# KeyboardMain.net
KiCad netlist of a schematic drawn in Altium Designer
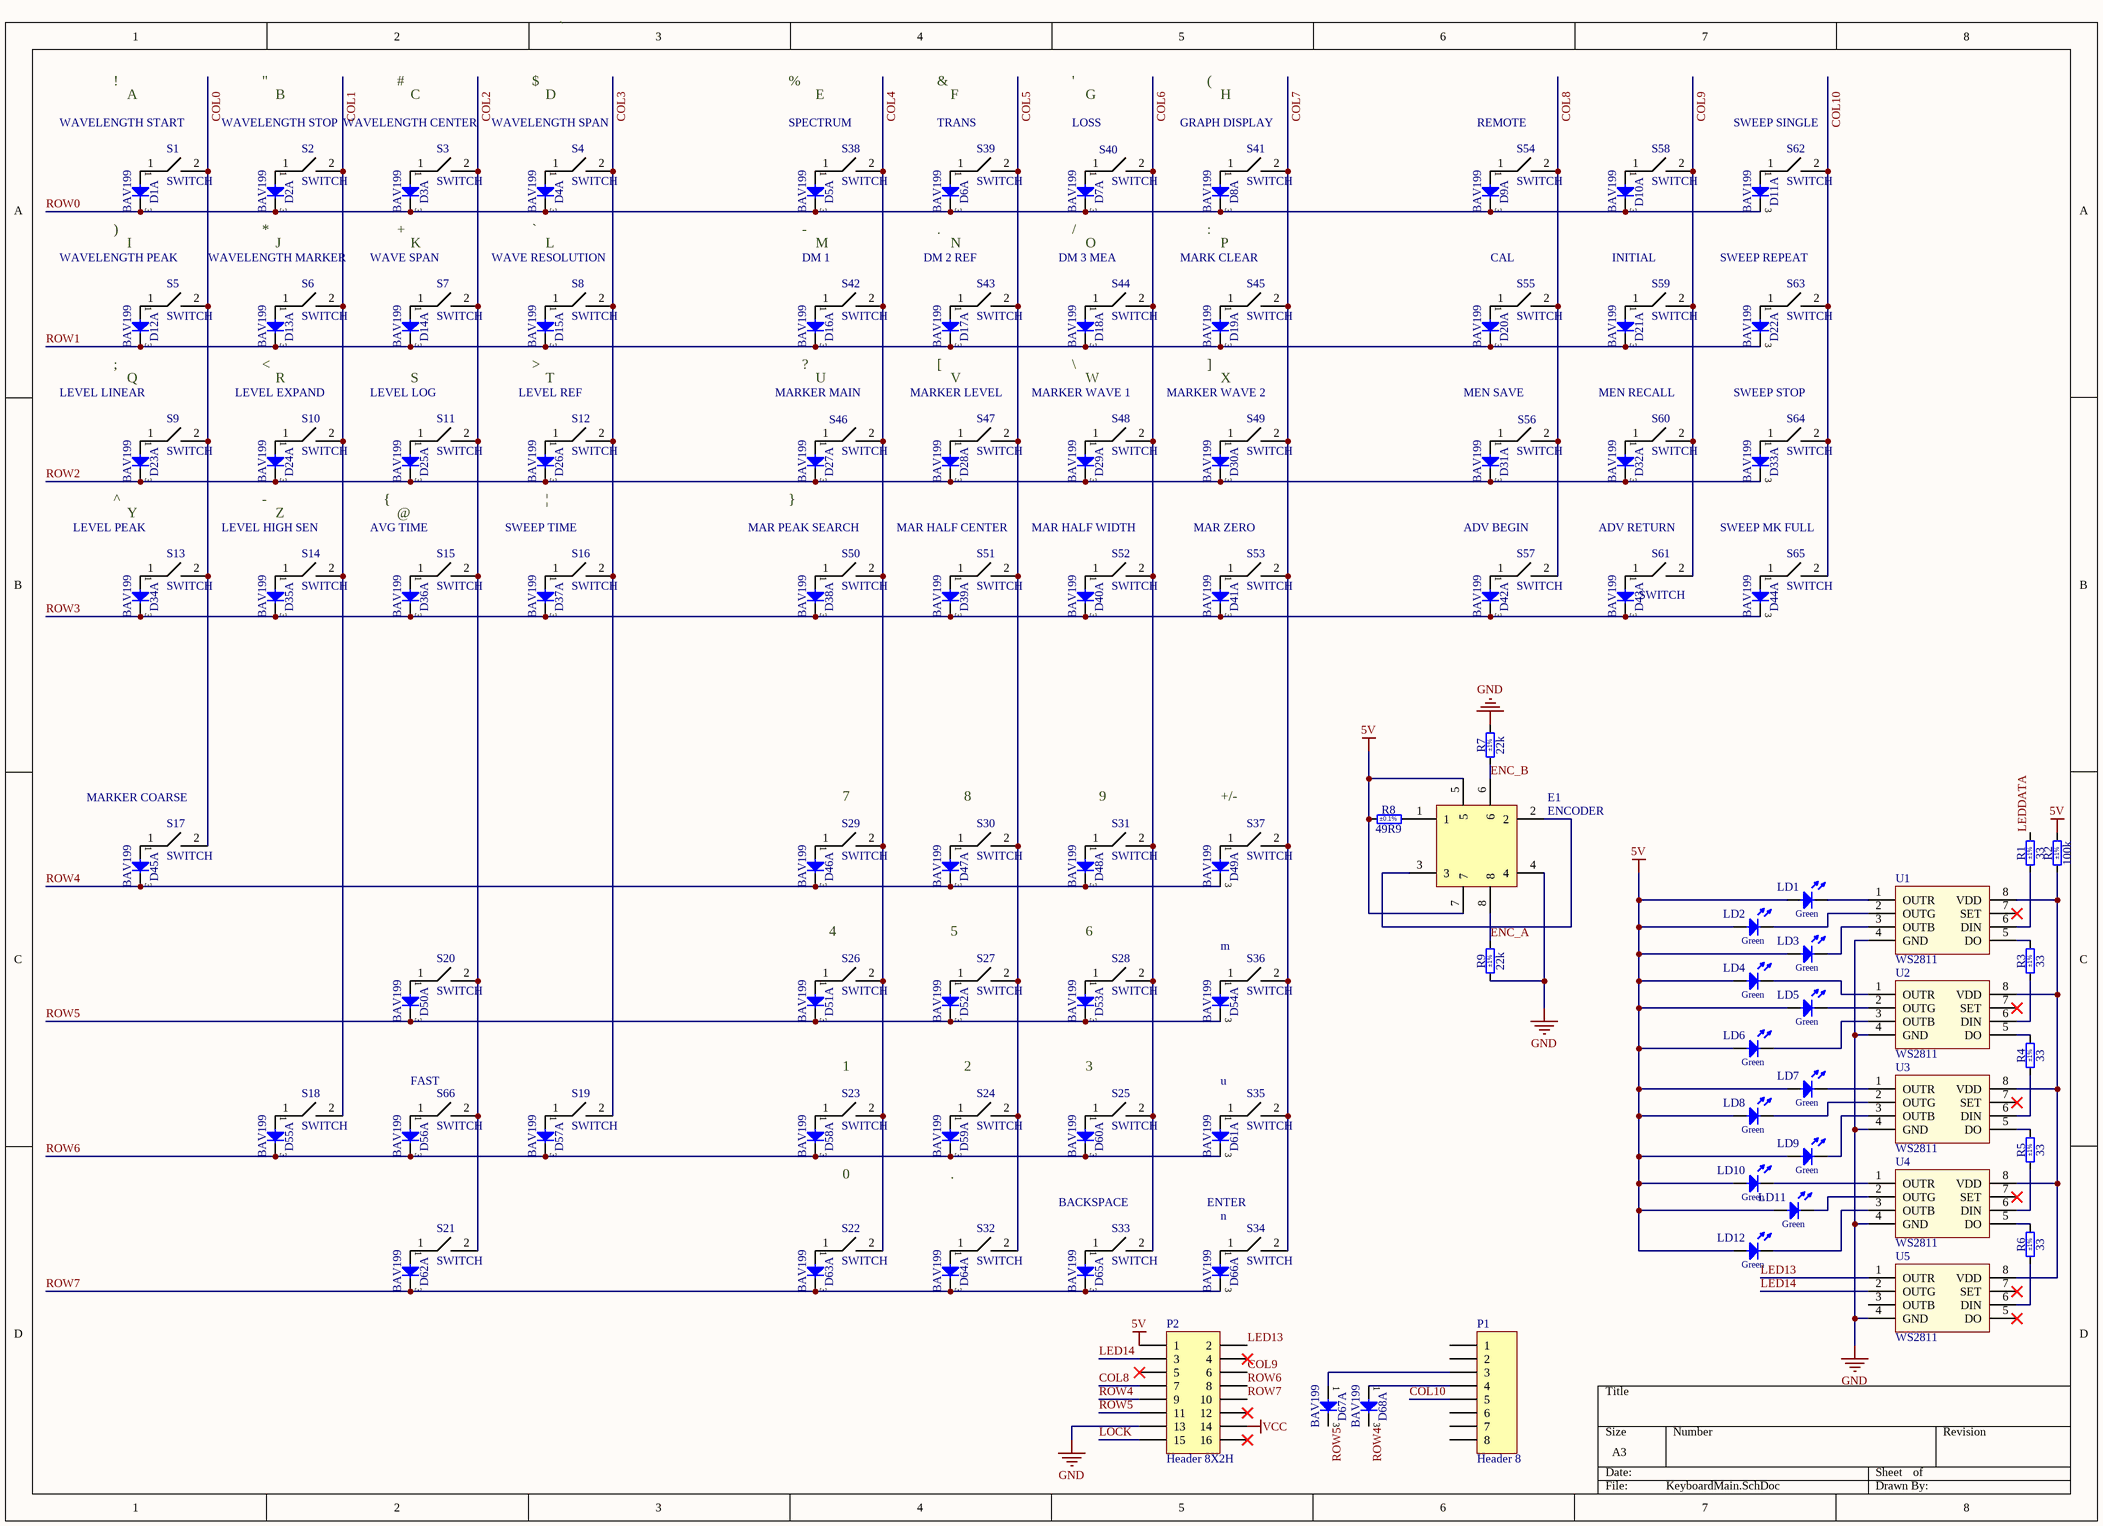
[diagram p0: KeyboardMain.SchDoc]

(export (version "E")
  (design (tool "Eeschema 10.0.6"))
  (components
    (comp (ref "D1")
      (value "BAV199")
      (footprint "SOT95P240X110-3N")
      (description "Serial Diode")
      (fields
        (field (name "VOLTAGE") "75V")
        (field (name "POWER") "250mW")
        (field (name "AUTHOR") "CERN DEM JMW")
      )
      (libsource (lib "ICs And Semiconductors") (part "Diode x2 A1C3_A3C2"))
    )
    (comp (ref "D2")
      (value "BAV199")
      (footprint "SOT95P240X110-3N")
      (description "Serial Diode")
      (fields
        (field (name "VOLTAGE") "75V")
        (field (name "POWER") "250mW")
        (field (name "AUTHOR") "CERN DEM JMW")
      )
      (libsource (lib "ICs And Semiconductors") (part "Diode x2 A1C3_A3C2"))
    )
    (comp (ref "D3")
      (value "BAV199")
      (footprint "SOT95P240X110-3N")
      (description "Serial Diode")
      (fields
        (field (name "VOLTAGE") "75V")
        (field (name "POWER") "250mW")
        (field (name "AUTHOR") "CERN DEM JMW")
      )
      (libsource (lib "ICs And Semiconductors") (part "Diode x2 A1C3_A3C2"))
    )
    (comp (ref "D4")
      (value "BAV199")
      (footprint "SOT95P240X110-3N")
      (description "Serial Diode")
      (fields
        (field (name "VOLTAGE") "75V")
        (field (name "POWER") "250mW")
        (field (name "AUTHOR") "CERN DEM JMW")
      )
      (libsource (lib "ICs And Semiconductors") (part "Diode x2 A1C3_A3C2"))
    )
    (comp (ref "D5")
      (value "BAV199")
      (footprint "SOT95P240X110-3N")
      (description "Serial Diode")
      (fields
        (field (name "VOLTAGE") "75V")
        (field (name "POWER") "250mW")
        (field (name "AUTHOR") "CERN DEM JMW")
      )
      (libsource (lib "ICs And Semiconductors") (part "Diode x2 A1C3_A3C2"))
    )
    (comp (ref "D6")
      (value "BAV199")
      (footprint "SOT95P240X110-3N")
      (description "Serial Diode")
      (fields
        (field (name "VOLTAGE") "75V")
        (field (name "POWER") "250mW")
        (field (name "AUTHOR") "CERN DEM JMW")
      )
      (libsource (lib "ICs And Semiconductors") (part "Diode x2 A1C3_A3C2"))
    )
    (comp (ref "D7")
      (value "BAV199")
      (footprint "SOT95P240X110-3N")
      (description "Serial Diode")
      (fields
        (field (name "VOLTAGE") "75V")
        (field (name "POWER") "250mW")
        (field (name "AUTHOR") "CERN DEM JMW")
      )
      (libsource (lib "ICs And Semiconductors") (part "Diode x2 A1C3_A3C2"))
    )
    (comp (ref "D8")
      (value "BAV199")
      (footprint "SOT95P240X110-3N")
      (description "Serial Diode")
      (fields
        (field (name "VOLTAGE") "75V")
        (field (name "POWER") "250mW")
        (field (name "AUTHOR") "CERN DEM JMW")
      )
      (libsource (lib "ICs And Semiconductors") (part "Diode x2 A1C3_A3C2"))
    )
    (comp (ref "D9")
      (value "BAV199")
      (footprint "SOT95P240X110-3N")
      (description "Serial Diode")
      (fields
        (field (name "VOLTAGE") "75V")
        (field (name "POWER") "250mW")
        (field (name "AUTHOR") "CERN DEM JMW")
      )
      (libsource (lib "ICs And Semiconductors") (part "Diode x2 A1C3_A3C2"))
    )
    (comp (ref "D10")
      (value "BAV199")
      (footprint "SOT95P240X110-3N")
      (description "Serial Diode")
      (fields
        (field (name "VOLTAGE") "75V")
        (field (name "POWER") "250mW")
        (field (name "AUTHOR") "CERN DEM JMW")
      )
      (libsource (lib "ICs And Semiconductors") (part "Diode x2 A1C3_A3C2"))
    )
    (comp (ref "D11")
      (value "BAV199")
      (footprint "SOT95P240X110-3N")
      (description "Serial Diode")
      (fields
        (field (name "VOLTAGE") "75V")
        (field (name "POWER") "250mW")
        (field (name "AUTHOR") "CERN DEM JMW")
      )
      (libsource (lib "ICs And Semiconductors") (part "Diode x2 A1C3_A3C2"))
    )
    (comp (ref "D12")
      (value "BAV199")
      (footprint "SOT95P240X110-3N")
      (description "Serial Diode")
      (fields
        (field (name "VOLTAGE") "75V")
        (field (name "POWER") "250mW")
        (field (name "AUTHOR") "CERN DEM JMW")
      )
      (libsource (lib "ICs And Semiconductors") (part "Diode x2 A1C3_A3C2"))
    )
    (comp (ref "D13")
      (value "BAV199")
      (footprint "SOT95P240X110-3N")
      (description "Serial Diode")
      (fields
        (field (name "VOLTAGE") "75V")
        (field (name "POWER") "250mW")
        (field (name "AUTHOR") "CERN DEM JMW")
      )
      (libsource (lib "ICs And Semiconductors") (part "Diode x2 A1C3_A3C2"))
    )
    (comp (ref "D14")
      (value "BAV199")
      (footprint "SOT95P240X110-3N")
      (description "Serial Diode")
      (fields
        (field (name "VOLTAGE") "75V")
        (field (name "POWER") "250mW")
        (field (name "AUTHOR") "CERN DEM JMW")
      )
      (libsource (lib "ICs And Semiconductors") (part "Diode x2 A1C3_A3C2"))
    )
    (comp (ref "D15")
      (value "BAV199")
      (footprint "SOT95P240X110-3N")
      (description "Serial Diode")
      (fields
        (field (name "VOLTAGE") "75V")
        (field (name "POWER") "250mW")
        (field (name "AUTHOR") "CERN DEM JMW")
      )
      (libsource (lib "ICs And Semiconductors") (part "Diode x2 A1C3_A3C2"))
    )
    (comp (ref "D16")
      (value "BAV199")
      (footprint "SOT95P240X110-3N")
      (description "Serial Diode")
      (fields
        (field (name "VOLTAGE") "75V")
        (field (name "POWER") "250mW")
        (field (name "AUTHOR") "CERN DEM JMW")
      )
      (libsource (lib "ICs And Semiconductors") (part "Diode x2 A1C3_A3C2"))
    )
    (comp (ref "D17")
      (value "BAV199")
      (footprint "SOT95P240X110-3N")
      (description "Serial Diode")
      (fields
        (field (name "VOLTAGE") "75V")
        (field (name "POWER") "250mW")
        (field (name "AUTHOR") "CERN DEM JMW")
      )
      (libsource (lib "ICs And Semiconductors") (part "Diode x2 A1C3_A3C2"))
    )
    (comp (ref "D18")
      (value "BAV199")
      (footprint "SOT95P240X110-3N")
      (description "Serial Diode")
      (fields
        (field (name "VOLTAGE") "75V")
        (field (name "POWER") "250mW")
        (field (name "AUTHOR") "CERN DEM JMW")
      )
      (libsource (lib "ICs And Semiconductors") (part "Diode x2 A1C3_A3C2"))
    )
    (comp (ref "D19")
      (value "BAV199")
      (footprint "SOT95P240X110-3N")
      (description "Serial Diode")
      (fields
        (field (name "VOLTAGE") "75V")
        (field (name "POWER") "250mW")
        (field (name "AUTHOR") "CERN DEM JMW")
      )
      (libsource (lib "ICs And Semiconductors") (part "Diode x2 A1C3_A3C2"))
    )
    (comp (ref "D20")
      (value "BAV199")
      (footprint "SOT95P240X110-3N")
      (description "Serial Diode")
      (fields
        (field (name "VOLTAGE") "75V")
        (field (name "POWER") "250mW")
        (field (name "AUTHOR") "CERN DEM JMW")
      )
      (libsource (lib "ICs And Semiconductors") (part "Diode x2 A1C3_A3C2"))
    )
    (comp (ref "D21")
      (value "BAV199")
      (footprint "SOT95P240X110-3N")
      (description "Serial Diode")
      (fields
        (field (name "VOLTAGE") "75V")
        (field (name "POWER") "250mW")
        (field (name "AUTHOR") "CERN DEM JMW")
      )
      (libsource (lib "ICs And Semiconductors") (part "Diode x2 A1C3_A3C2"))
    )
    (comp (ref "D22")
      (value "BAV199")
      (footprint "SOT95P240X110-3N")
      (description "Serial Diode")
      (fields
        (field (name "VOLTAGE") "75V")
        (field (name "POWER") "250mW")
        (field (name "AUTHOR") "CERN DEM JMW")
      )
      (libsource (lib "ICs And Semiconductors") (part "Diode x2 A1C3_A3C2"))
    )
    (comp (ref "D23")
      (value "BAV199")
      (footprint "SOT95P240X110-3N")
      (description "Serial Diode")
      (fields
        (field (name "VOLTAGE") "75V")
        (field (name "POWER") "250mW")
        (field (name "AUTHOR") "CERN DEM JMW")
      )
      (libsource (lib "ICs And Semiconductors") (part "Diode x2 A1C3_A3C2"))
    )
    (comp (ref "D24")
      (value "BAV199")
      (footprint "SOT95P240X110-3N")
      (description "Serial Diode")
      (fields
        (field (name "VOLTAGE") "75V")
        (field (name "POWER") "250mW")
        (field (name "AUTHOR") "CERN DEM JMW")
      )
      (libsource (lib "ICs And Semiconductors") (part "Diode x2 A1C3_A3C2"))
    )
    (comp (ref "D25")
      (value "BAV199")
      (footprint "SOT95P240X110-3N")
      (description "Serial Diode")
      (fields
        (field (name "VOLTAGE") "75V")
        (field (name "POWER") "250mW")
        (field (name "AUTHOR") "CERN DEM JMW")
      )
      (libsource (lib "ICs And Semiconductors") (part "Diode x2 A1C3_A3C2"))
    )
    (comp (ref "D26")
      (value "BAV199")
      (footprint "SOT95P240X110-3N")
      (description "Serial Diode")
      (fields
        (field (name "VOLTAGE") "75V")
        (field (name "POWER") "250mW")
        (field (name "AUTHOR") "CERN DEM JMW")
      )
      (libsource (lib "ICs And Semiconductors") (part "Diode x2 A1C3_A3C2"))
    )
    (comp (ref "D27")
      (value "BAV199")
      (footprint "SOT95P240X110-3N")
      (description "Serial Diode")
      (fields
        (field (name "VOLTAGE") "75V")
        (field (name "POWER") "250mW")
        (field (name "AUTHOR") "CERN DEM JMW")
      )
      (libsource (lib "ICs And Semiconductors") (part "Diode x2 A1C3_A3C2"))
    )
    (comp (ref "D28")
      (value "BAV199")
      (footprint "SOT95P240X110-3N")
      (description "Serial Diode")
      (fields
        (field (name "VOLTAGE") "75V")
        (field (name "POWER") "250mW")
        (field (name "AUTHOR") "CERN DEM JMW")
      )
      (libsource (lib "ICs And Semiconductors") (part "Diode x2 A1C3_A3C2"))
    )
    (comp (ref "D29")
      (value "BAV199")
      (footprint "SOT95P240X110-3N")
      (description "Serial Diode")
      (fields
        (field (name "VOLTAGE") "75V")
        (field (name "POWER") "250mW")
        (field (name "AUTHOR") "CERN DEM JMW")
      )
      (libsource (lib "ICs And Semiconductors") (part "Diode x2 A1C3_A3C2"))
    )
    (comp (ref "D30")
      (value "BAV199")
      (footprint "SOT95P240X110-3N")
      (description "Serial Diode")
      (fields
        (field (name "VOLTAGE") "75V")
        (field (name "POWER") "250mW")
        (field (name "AUTHOR") "CERN DEM JMW")
      )
      (libsource (lib "ICs And Semiconductors") (part "Diode x2 A1C3_A3C2"))
    )
    (comp (ref "D31")
      (value "BAV199")
      (footprint "SOT95P240X110-3N")
      (description "Serial Diode")
      (fields
        (field (name "VOLTAGE") "75V")
        (field (name "POWER") "250mW")
        (field (name "AUTHOR") "CERN DEM JMW")
      )
      (libsource (lib "ICs And Semiconductors") (part "Diode x2 A1C3_A3C2"))
    )
    (comp (ref "D32")
      (value "BAV199")
      (footprint "SOT95P240X110-3N")
      (description "Serial Diode")
      (fields
        (field (name "VOLTAGE") "75V")
        (field (name "POWER") "250mW")
        (field (name "AUTHOR") "CERN DEM JMW")
      )
      (libsource (lib "ICs And Semiconductors") (part "Diode x2 A1C3_A3C2"))
    )
    (comp (ref "D33")
      (value "BAV199")
      (footprint "SOT95P240X110-3N")
      (description "Serial Diode")
      (fields
        (field (name "VOLTAGE") "75V")
        (field (name "POWER") "250mW")
        (field (name "AUTHOR") "CERN DEM JMW")
      )
      (libsource (lib "ICs And Semiconductors") (part "Diode x2 A1C3_A3C2"))
    )
    (comp (ref "D34")
      (value "BAV199")
      (footprint "SOT95P240X110-3N")
      (description "Serial Diode")
      (fields
        (field (name "VOLTAGE") "75V")
        (field (name "POWER") "250mW")
        (field (name "AUTHOR") "CERN DEM JMW")
      )
      (libsource (lib "ICs And Semiconductors") (part "Diode x2 A1C3_A3C2"))
    )
    (comp (ref "D35")
      (value "BAV199")
      (footprint "SOT95P240X110-3N")
      (description "Serial Diode")
      (fields
        (field (name "VOLTAGE") "75V")
        (field (name "POWER") "250mW")
        (field (name "AUTHOR") "CERN DEM JMW")
      )
      (libsource (lib "ICs And Semiconductors") (part "Diode x2 A1C3_A3C2"))
    )
    (comp (ref "D36")
      (value "BAV199")
      (footprint "SOT95P240X110-3N")
      (description "Serial Diode")
      (fields
        (field (name "VOLTAGE") "75V")
        (field (name "POWER") "250mW")
        (field (name "AUTHOR") "CERN DEM JMW")
      )
      (libsource (lib "ICs And Semiconductors") (part "Diode x2 A1C3_A3C2"))
    )
    (comp (ref "D37")
      (value "BAV199")
      (footprint "SOT95P240X110-3N")
      (description "Serial Diode")
      (fields
        (field (name "VOLTAGE") "75V")
        (field (name "POWER") "250mW")
        (field (name "AUTHOR") "CERN DEM JMW")
      )
      (libsource (lib "ICs And Semiconductors") (part "Diode x2 A1C3_A3C2"))
    )
    (comp (ref "D38")
      (value "BAV199")
      (footprint "SOT95P240X110-3N")
      (description "Serial Diode")
      (fields
        (field (name "VOLTAGE") "75V")
        (field (name "POWER") "250mW")
        (field (name "AUTHOR") "CERN DEM JMW")
      )
      (libsource (lib "ICs And Semiconductors") (part "Diode x2 A1C3_A3C2"))
    )
    (comp (ref "D39")
      (value "BAV199")
      (footprint "SOT95P240X110-3N")
      (description "Serial Diode")
      (fields
        (field (name "VOLTAGE") "75V")
        (field (name "POWER") "250mW")
        (field (name "AUTHOR") "CERN DEM JMW")
      )
      (libsource (lib "ICs And Semiconductors") (part "Diode x2 A1C3_A3C2"))
    )
    (comp (ref "D40")
      (value "BAV199")
      (footprint "SOT95P240X110-3N")
      (description "Serial Diode")
      (fields
        (field (name "VOLTAGE") "75V")
        (field (name "POWER") "250mW")
        (field (name "AUTHOR") "CERN DEM JMW")
      )
      (libsource (lib "ICs And Semiconductors") (part "Diode x2 A1C3_A3C2"))
    )
    (comp (ref "D41")
      (value "BAV199")
      (footprint "SOT95P240X110-3N")
      (description "Serial Diode")
      (fields
        (field (name "VOLTAGE") "75V")
        (field (name "POWER") "250mW")
        (field (name "AUTHOR") "CERN DEM JMW")
      )
      (libsource (lib "ICs And Semiconductors") (part "Diode x2 A1C3_A3C2"))
    )
    (comp (ref "D42")
      (value "BAV199")
      (footprint "SOT95P240X110-3N")
      (description "Serial Diode")
      (fields
        (field (name "VOLTAGE") "75V")
        (field (name "POWER") "250mW")
        (field (name "AUTHOR") "CERN DEM JMW")
      )
      (libsource (lib "ICs And Semiconductors") (part "Diode x2 A1C3_A3C2"))
    )
    (comp (ref "D43")
      (value "BAV199")
      (footprint "SOT95P240X110-3N")
      (description "Serial Diode")
      (fields
        (field (name "VOLTAGE") "75V")
        (field (name "POWER") "250mW")
        (field (name "AUTHOR") "CERN DEM JMW")
      )
      (libsource (lib "ICs And Semiconductors") (part "Diode x2 A1C3_A3C2"))
    )
    (comp (ref "D44")
      (value "BAV199")
      (footprint "SOT95P240X110-3N")
      (description "Serial Diode")
      (fields
        (field (name "VOLTAGE") "75V")
        (field (name "POWER") "250mW")
        (field (name "AUTHOR") "CERN DEM JMW")
      )
      (libsource (lib "ICs And Semiconductors") (part "Diode x2 A1C3_A3C2"))
    )
    (comp (ref "D45")
      (value "BAV199")
      (footprint "SOT95P240X110-3N")
      (description "Serial Diode")
      (fields
        (field (name "VOLTAGE") "75V")
        (field (name "POWER") "250mW")
        (field (name "AUTHOR") "CERN DEM JMW")
      )
      (libsource (lib "ICs And Semiconductors") (part "Diode x2 A1C3_A3C2"))
    )
    (comp (ref "D46")
      (value "BAV199")
      (footprint "SOT95P240X110-3N")
      (description "Serial Diode")
      (fields
        (field (name "VOLTAGE") "75V")
        (field (name "POWER") "250mW")
        (field (name "AUTHOR") "CERN DEM JMW")
      )
      (libsource (lib "ICs And Semiconductors") (part "Diode x2 A1C3_A3C2"))
    )
    (comp (ref "D47")
      (value "BAV199")
      (footprint "SOT95P240X110-3N")
      (description "Serial Diode")
      (fields
        (field (name "VOLTAGE") "75V")
        (field (name "POWER") "250mW")
        (field (name "AUTHOR") "CERN DEM JMW")
      )
      (libsource (lib "ICs And Semiconductors") (part "Diode x2 A1C3_A3C2"))
    )
    (comp (ref "D48")
      (value "BAV199")
      (footprint "SOT95P240X110-3N")
      (description "Serial Diode")
      (fields
        (field (name "VOLTAGE") "75V")
        (field (name "POWER") "250mW")
        (field (name "AUTHOR") "CERN DEM JMW")
      )
      (libsource (lib "ICs And Semiconductors") (part "Diode x2 A1C3_A3C2"))
    )
    (comp (ref "D49")
      (value "BAV199")
      (footprint "SOT95P240X110-3N")
      (description "Serial Diode")
      (fields
        (field (name "VOLTAGE") "75V")
        (field (name "POWER") "250mW")
        (field (name "AUTHOR") "CERN DEM JMW")
      )
      (libsource (lib "ICs And Semiconductors") (part "Diode x2 A1C3_A3C2"))
    )
    (comp (ref "D50")
      (value "BAV199")
      (footprint "SOT95P240X110-3N")
      (description "Serial Diode")
      (fields
        (field (name "VOLTAGE") "75V")
        (field (name "POWER") "250mW")
        (field (name "AUTHOR") "CERN DEM JMW")
      )
      (libsource (lib "ICs And Semiconductors") (part "Diode x2 A1C3_A3C2"))
    )
    (comp (ref "D51")
      (value "BAV199")
      (footprint "SOT95P240X110-3N")
      (description "Serial Diode")
      (fields
        (field (name "VOLTAGE") "75V")
        (field (name "POWER") "250mW")
        (field (name "AUTHOR") "CERN DEM JMW")
      )
      (libsource (lib "ICs And Semiconductors") (part "Diode x2 A1C3_A3C2"))
    )
    (comp (ref "D52")
      (value "BAV199")
      (footprint "SOT95P240X110-3N")
      (description "Serial Diode")
      (fields
        (field (name "VOLTAGE") "75V")
        (field (name "POWER") "250mW")
        (field (name "AUTHOR") "CERN DEM JMW")
      )
      (libsource (lib "ICs And Semiconductors") (part "Diode x2 A1C3_A3C2"))
    )
    (comp (ref "D53")
      (value "BAV199")
      (footprint "SOT95P240X110-3N")
      (description "Serial Diode")
      (fields
        (field (name "VOLTAGE") "75V")
        (field (name "POWER") "250mW")
        (field (name "AUTHOR") "CERN DEM JMW")
      )
      (libsource (lib "ICs And Semiconductors") (part "Diode x2 A1C3_A3C2"))
    )
    (comp (ref "D54")
      (value "BAV199")
      (footprint "SOT95P240X110-3N")
      (description "Serial Diode")
      (fields
        (field (name "VOLTAGE") "75V")
        (field (name "POWER") "250mW")
        (field (name "AUTHOR") "CERN DEM JMW")
      )
      (libsource (lib "ICs And Semiconductors") (part "Diode x2 A1C3_A3C2"))
    )
    (comp (ref "D55")
      (value "BAV199")
      (footprint "SOT95P240X110-3N")
      (description "Serial Diode")
      (fields
        (field (name "VOLTAGE") "75V")
        (field (name "POWER") "250mW")
        (field (name "AUTHOR") "CERN DEM JMW")
      )
      (libsource (lib "ICs And Semiconductors") (part "Diode x2 A1C3_A3C2"))
    )
    (comp (ref "D56")
      (value "BAV199")
      (footprint "SOT95P240X110-3N")
      (description "Serial Diode")
      (fields
        (field (name "VOLTAGE") "75V")
        (field (name "POWER") "250mW")
        (field (name "AUTHOR") "CERN DEM JMW")
      )
      (libsource (lib "ICs And Semiconductors") (part "Diode x2 A1C3_A3C2"))
    )
    (comp (ref "D57")
      (value "BAV199")
      (footprint "SOT95P240X110-3N")
      (description "Serial Diode")
      (fields
        (field (name "VOLTAGE") "75V")
        (field (name "POWER") "250mW")
        (field (name "AUTHOR") "CERN DEM JMW")
      )
      (libsource (lib "ICs And Semiconductors") (part "Diode x2 A1C3_A3C2"))
    )
    (comp (ref "D58")
      (value "BAV199")
      (footprint "SOT95P240X110-3N")
      (description "Serial Diode")
      (fields
        (field (name "VOLTAGE") "75V")
        (field (name "POWER") "250mW")
        (field (name "AUTHOR") "CERN DEM JMW")
      )
      (libsource (lib "ICs And Semiconductors") (part "Diode x2 A1C3_A3C2"))
    )
    (comp (ref "D59")
      (value "BAV199")
      (footprint "SOT95P240X110-3N")
      (description "Serial Diode")
      (fields
        (field (name "VOLTAGE") "75V")
        (field (name "POWER") "250mW")
        (field (name "AUTHOR") "CERN DEM JMW")
      )
      (libsource (lib "ICs And Semiconductors") (part "Diode x2 A1C3_A3C2"))
    )
    (comp (ref "D60")
      (value "BAV199")
      (footprint "SOT95P240X110-3N")
      (description "Serial Diode")
      (fields
        (field (name "VOLTAGE") "75V")
        (field (name "POWER") "250mW")
        (field (name "AUTHOR") "CERN DEM JMW")
      )
      (libsource (lib "ICs And Semiconductors") (part "Diode x2 A1C3_A3C2"))
    )
    (comp (ref "D61")
      (value "BAV199")
      (footprint "SOT95P240X110-3N")
      (description "Serial Diode")
      (fields
        (field (name "VOLTAGE") "75V")
        (field (name "POWER") "250mW")
        (field (name "AUTHOR") "CERN DEM JMW")
      )
      (libsource (lib "ICs And Semiconductors") (part "Diode x2 A1C3_A3C2"))
    )
    (comp (ref "D62")
      (value "BAV199")
      (footprint "SOT95P240X110-3N")
      (description "Serial Diode")
      (fields
        (field (name "VOLTAGE") "75V")
        (field (name "POWER") "250mW")
        (field (name "AUTHOR") "CERN DEM JMW")
      )
      (libsource (lib "ICs And Semiconductors") (part "Diode x2 A1C3_A3C2"))
    )
    (comp (ref "D63")
      (value "BAV199")
      (footprint "SOT95P240X110-3N")
      (description "Serial Diode")
      (fields
        (field (name "VOLTAGE") "75V")
        (field (name "POWER") "250mW")
        (field (name "AUTHOR") "CERN DEM JMW")
      )
      (libsource (lib "ICs And Semiconductors") (part "Diode x2 A1C3_A3C2"))
    )
    (comp (ref "D64")
      (value "BAV199")
      (footprint "SOT95P240X110-3N")
      (description "Serial Diode")
      (fields
        (field (name "VOLTAGE") "75V")
        (field (name "POWER") "250mW")
        (field (name "AUTHOR") "CERN DEM JMW")
      )
      (libsource (lib "ICs And Semiconductors") (part "Diode x2 A1C3_A3C2"))
    )
    (comp (ref "D65")
      (value "BAV199")
      (footprint "SOT95P240X110-3N")
      (description "Serial Diode")
      (fields
        (field (name "VOLTAGE") "75V")
        (field (name "POWER") "250mW")
        (field (name "AUTHOR") "CERN DEM JMW")
      )
      (libsource (lib "ICs And Semiconductors") (part "Diode x2 A1C3_A3C2"))
    )
    (comp (ref "D66")
      (value "BAV199")
      (footprint "SOT95P240X110-3N")
      (description "Serial Diode")
      (fields
        (field (name "VOLTAGE") "75V")
        (field (name "POWER") "250mW")
        (field (name "AUTHOR") "CERN DEM JMW")
      )
      (libsource (lib "ICs And Semiconductors") (part "Diode x2 A1C3_A3C2"))
    )
    (comp (ref "D67")
      (value "BAV199")
      (footprint "SOT95P240X110-3N")
      (description "Serial Diode")
      (fields
        (field (name "VOLTAGE") "75V")
        (field (name "POWER") "250mW")
        (field (name "AUTHOR") "CERN DEM JMW")
      )
      (libsource (lib "ICs And Semiconductors") (part "Diode x2 A1C3_A3C2"))
    )
    (comp (ref "D68")
      (value "BAV199")
      (footprint "SOT95P240X110-3N")
      (description "Serial Diode")
      (fields
        (field (name "VOLTAGE") "75V")
        (field (name "POWER") "250mW")
        (field (name "AUTHOR") "CERN DEM JMW")
      )
      (libsource (lib "ICs And Semiconductors") (part "Diode x2 A1C3_A3C2"))
    )
    (comp (ref "E1") (value "ENCODER") (footprint "ENCODER") (libsource (lib "OSA") (part "ENCODER")))
    (comp (ref "LD1")
      (value "Green")
      (footprint "LED_3MM_GREEN_1C-2A")
      (description "LED Green 1C 2A")
      (fields
        (field (name "PART NUMBER") "LED_AVAGO_HLMP-1790")
        (field (name "MANUFACTURER") "AVAGO TECHNOLOGIES")
        (field (name "AUTHOR") "CERN DEM JLC")
      )
      (libsource (lib "ICs And Semiconductors") (part "LED Green 1C 2A"))
    )
    (comp (ref "LD2")
      (value "Green")
      (footprint "LED_3MM_GREEN_1C-2A")
      (description "LED Green 1C 2A")
      (fields
        (field (name "PART NUMBER") "LED_AVAGO_HLMP-1790")
        (field (name "MANUFACTURER") "AVAGO TECHNOLOGIES")
        (field (name "AUTHOR") "CERN DEM JLC")
      )
      (libsource (lib "ICs And Semiconductors") (part "LED Green 1C 2A"))
    )
    (comp (ref "LD3")
      (value "Green")
      (footprint "LED_3MM_GREEN_1C-2A")
      (description "LED Green 1C 2A")
      (fields
        (field (name "PART NUMBER") "LED_AVAGO_HLMP-1790")
        (field (name "MANUFACTURER") "AVAGO TECHNOLOGIES")
        (field (name "AUTHOR") "CERN DEM JLC")
      )
      (libsource (lib "ICs And Semiconductors") (part "LED Green 1C 2A"))
    )
    (comp (ref "LD4")
      (value "Green")
      (footprint "LED_3MM_GREEN_1C-2A")
      (description "LED Green 1C 2A")
      (fields
        (field (name "PART NUMBER") "LED_AVAGO_HLMP-1790")
        (field (name "MANUFACTURER") "AVAGO TECHNOLOGIES")
        (field (name "AUTHOR") "CERN DEM JLC")
      )
      (libsource (lib "ICs And Semiconductors") (part "LED Green 1C 2A"))
    )
    (comp (ref "LD5")
      (value "Green")
      (footprint "LED_3MM_GREEN_1C-2A")
      (description "LED Green 1C 2A")
      (fields
        (field (name "PART NUMBER") "LED_AVAGO_HLMP-1790")
        (field (name "MANUFACTURER") "AVAGO TECHNOLOGIES")
        (field (name "AUTHOR") "CERN DEM JLC")
      )
      (libsource (lib "ICs And Semiconductors") (part "LED Green 1C 2A"))
    )
    (comp (ref "LD6")
      (value "Green")
      (footprint "LED_3MM_GREEN_1C-2A")
      (description "LED Green 1C 2A")
      (fields
        (field (name "PART NUMBER") "LED_AVAGO_HLMP-1790")
        (field (name "MANUFACTURER") "AVAGO TECHNOLOGIES")
        (field (name "AUTHOR") "CERN DEM JLC")
      )
      (libsource (lib "ICs And Semiconductors") (part "LED Green 1C 2A"))
    )
    (comp (ref "LD7")
      (value "Green")
      (footprint "LED_3MM_GREEN_1C-2A")
      (description "LED Green 1C 2A")
      (fields
        (field (name "PART NUMBER") "LED_AVAGO_HLMP-1790")
        (field (name "MANUFACTURER") "AVAGO TECHNOLOGIES")
        (field (name "AUTHOR") "CERN DEM JLC")
      )
      (libsource (lib "ICs And Semiconductors") (part "LED Green 1C 2A"))
    )
    (comp (ref "LD8")
      (value "Green")
      (footprint "LED_3MM_GREEN_1C-2A")
      (description "LED Green 1C 2A")
      (fields
        (field (name "PART NUMBER") "LED_AVAGO_HLMP-1790")
        (field (name "MANUFACTURER") "AVAGO TECHNOLOGIES")
        (field (name "AUTHOR") "CERN DEM JLC")
      )
      (libsource (lib "ICs And Semiconductors") (part "LED Green 1C 2A"))
    )
    (comp (ref "LD9")
      (value "Green")
      (footprint "LED_3MM_GREEN_1C-2A")
      (description "LED Green 1C 2A")
      (fields
        (field (name "PART NUMBER") "LED_AVAGO_HLMP-1790")
        (field (name "MANUFACTURER") "AVAGO TECHNOLOGIES")
        (field (name "AUTHOR") "CERN DEM JLC")
      )
      (libsource (lib "ICs And Semiconductors") (part "LED Green 1C 2A"))
    )
    (comp (ref "LD10")
      (value "Green")
      (footprint "LED_3MM_GREEN_1C-2A")
      (description "LED Green 1C 2A")
      (fields
        (field (name "PART NUMBER") "LED_AVAGO_HLMP-1790")
        (field (name "MANUFACTURER") "AVAGO TECHNOLOGIES")
        (field (name "AUTHOR") "CERN DEM JLC")
      )
      (libsource (lib "ICs And Semiconductors") (part "LED Green 1C 2A"))
    )
    (comp (ref "LD11")
      (value "Green")
      (footprint "LED_3MM_GREEN_1C-2A")
      (description "LED Green 1C 2A")
      (fields
        (field (name "PART NUMBER") "LED_AVAGO_HLMP-1790")
        (field (name "MANUFACTURER") "AVAGO TECHNOLOGIES")
        (field (name "AUTHOR") "CERN DEM JLC")
      )
      (libsource (lib "ICs And Semiconductors") (part "LED Green 1C 2A"))
    )
    (comp (ref "LD12")
      (value "Green")
      (footprint "LED_3MM_GREEN_1C-2A")
      (description "LED Green 1C 2A")
      (fields
        (field (name "PART NUMBER") "LED_AVAGO_HLMP-1790")
        (field (name "MANUFACTURER") "AVAGO TECHNOLOGIES")
        (field (name "AUTHOR") "CERN DEM JLC")
      )
      (libsource (lib "ICs And Semiconductors") (part "LED Green 1C 2A"))
    )
    (comp (ref "P1")
      (value "Header 8")
      (footprint "HDR1X8")
      (description "Header, 8-Pin")
      (fields (field (name "PUBLISHER") "Altium Limited"))
      (libsource (lib "Miscellaneous Connectors") (part "Header 8"))
    )
    (comp (ref "P2")
      (value "Header 8X2H")
      (footprint "HDR2X8H")
      (description "Header, 8-Pin, Dual row, Right Angle")
      (fields (field (name "PUBLISHER") "Altium Limited"))
      (libsource (lib "Miscellaneous Connectors") (part "Header 8X2H"))
    )
    (comp (ref "R1")
      (value "33")
      (footprint "RESC2012X60N")
      (description "Resistor - 1%")
      (fields
        (field (name "TOLERANCE") "±1%")
        (field (name "PART NUMBER") "R0805_33R_1%_0.125W_100PPM")
        (field (name "POWER") "0.125W")
        (field (name "AUTHOR") "CERN DEM JLC")
      )
      (libsource (lib "Resistors") (part "Resistor - 1%"))
    )
    (comp (ref "R2")
      (value "100k")
      (footprint "RESC2012X60N")
      (description "Resistor - 1%")
      (fields
        (field (name "TOLERANCE") "±1%")
        (field (name "PART NUMBER") "R0805_100K_1%_0.125W_100PPM")
        (field (name "POWER") "0.125W")
        (field (name "AUTHOR") "CERN DEM JLC")
      )
      (libsource (lib "Resistors") (part "Resistor - 1%"))
    )
    (comp (ref "R3")
      (value "33")
      (footprint "RESC2012X60N")
      (description "Resistor - 1%")
      (fields
        (field (name "TOLERANCE") "±1%")
        (field (name "PART NUMBER") "R0805_33R_1%_0.125W_100PPM")
        (field (name "POWER") "0.125W")
        (field (name "AUTHOR") "CERN DEM JLC")
      )
      (libsource (lib "Resistors") (part "Resistor - 1%"))
    )
    (comp (ref "R4")
      (value "33")
      (footprint "RESC2012X60N")
      (description "Resistor - 1%")
      (fields
        (field (name "TOLERANCE") "±1%")
        (field (name "PART NUMBER") "R0805_33R_1%_0.125W_100PPM")
        (field (name "POWER") "0.125W")
        (field (name "AUTHOR") "CERN DEM JLC")
      )
      (libsource (lib "Resistors") (part "Resistor - 1%"))
    )
    (comp (ref "R5")
      (value "33")
      (footprint "RESC2012X60N")
      (description "Resistor - 1%")
      (fields
        (field (name "TOLERANCE") "±1%")
        (field (name "PART NUMBER") "R0805_33R_1%_0.125W_100PPM")
        (field (name "POWER") "0.125W")
        (field (name "AUTHOR") "CERN DEM JLC")
      )
      (libsource (lib "Resistors") (part "Resistor - 1%"))
    )
    (comp (ref "R6")
      (value "33")
      (footprint "RESC2012X60N")
      (description "Resistor - 1%")
      (fields
        (field (name "TOLERANCE") "±1%")
        (field (name "PART NUMBER") "R0805_33R_1%_0.125W_100PPM")
        (field (name "POWER") "0.125W")
        (field (name "AUTHOR") "CERN DEM JLC")
      )
      (libsource (lib "Resistors") (part "Resistor - 1%"))
    )
    (comp (ref "R7")
      (value "22k")
      (footprint "RESC2012X60N")
      (description "Resistor - 1%")
      (fields
        (field (name "TOLERANCE") "±1%")
        (field (name "PART NUMBER") "R0805_22K_1%_0.125W_100PPM")
        (field (name "POWER") "0.125W")
        (field (name "AUTHOR") "CERN DEM JLC")
      )
      (libsource (lib "Resistors") (part "Resistor - 1%"))
    )
    (comp (ref "R8")
      (value "49R9")
      (footprint "RESC2012X60N")
      (description "Resistor - 0.1%")
      (fields
        (field (name "TOLERANCE") "±0.1%")
        (field (name "PART NUMBER") "R0805_49R9_0.1%_0.125W_25PPM")
        (field (name "POWER") "0.125W")
        (field (name "AUTHOR") "CERN DEM JLC")
      )
      (libsource (lib "Resistors") (part "Resistor - 0.1%"))
    )
    (comp (ref "R9")
      (value "22k")
      (footprint "RESC2012X60N")
      (description "Resistor - 1%")
      (fields
        (field (name "TOLERANCE") "±1%")
        (field (name "PART NUMBER") "R0805_22K_1%_0.125W_100PPM")
        (field (name "POWER") "0.125W")
        (field (name "AUTHOR") "CERN DEM JLC")
      )
      (libsource (lib "Resistors") (part "Resistor - 1%"))
    )
    (comp (ref "S1") (value "SWITCH") (footprint "SWITCH") (libsource (lib "OSA") (part "SWITCH")))
    (comp (ref "S2") (value "SWITCH") (footprint "SWITCH") (libsource (lib "OSA") (part "SWITCH")))
    (comp (ref "S3") (value "SWITCH") (footprint "SWITCH") (libsource (lib "OSA") (part "SWITCH")))
    (comp (ref "S4") (value "SWITCH") (footprint "SWITCH") (libsource (lib "OSA") (part "SWITCH")))
    (comp (ref "S5") (value "SWITCH") (footprint "SWITCH") (libsource (lib "OSA") (part "SWITCH")))
    (comp (ref "S6") (value "SWITCH") (footprint "SWITCH") (libsource (lib "OSA") (part "SWITCH")))
    (comp (ref "S7") (value "SWITCH") (footprint "SWITCH") (libsource (lib "OSA") (part "SWITCH")))
    (comp (ref "S8") (value "SWITCH") (footprint "SWITCH") (libsource (lib "OSA") (part "SWITCH")))
    (comp (ref "S9") (value "SWITCH") (footprint "SWITCH") (libsource (lib "OSA") (part "SWITCH")))
    (comp (ref "S10") (value "SWITCH") (footprint "SWITCH") (libsource (lib "OSA") (part "SWITCH")))
    (comp (ref "S11") (value "SWITCH") (footprint "SWITCH") (libsource (lib "OSA") (part "SWITCH")))
    (comp (ref "S12") (value "SWITCH") (footprint "SWITCH") (libsource (lib "OSA") (part "SWITCH")))
    (comp (ref "S13") (value "SWITCH") (footprint "SWITCH") (libsource (lib "OSA") (part "SWITCH")))
    (comp (ref "S14") (value "SWITCH") (footprint "SWITCH") (libsource (lib "OSA") (part "SWITCH")))
    (comp (ref "S15") (value "SWITCH") (footprint "SWITCH") (libsource (lib "OSA") (part "SWITCH")))
    (comp (ref "S16") (value "SWITCH") (footprint "SWITCH") (libsource (lib "OSA") (part "SWITCH")))
    (comp (ref "S17") (value "SWITCH") (footprint "SWITCH") (libsource (lib "OSA") (part "SWITCH")))
    (comp (ref "S18") (value "SWITCH") (footprint "SWITCH") (libsource (lib "OSA") (part "SWITCH")))
    (comp (ref "S19") (value "SWITCH") (footprint "SWITCH") (libsource (lib "OSA") (part "SWITCH")))
    (comp (ref "S20") (value "SWITCH") (footprint "SWITCH") (libsource (lib "OSA") (part "SWITCH")))
    (comp (ref "S21") (value "SWITCH") (footprint "SWITCH") (libsource (lib "OSA") (part "SWITCH")))
    (comp (ref "S22") (value "SWITCH") (footprint "SWITCH") (libsource (lib "OSA") (part "SWITCH")))
    (comp (ref "S23") (value "SWITCH") (footprint "SWITCH") (libsource (lib "OSA") (part "SWITCH")))
    (comp (ref "S24") (value "SWITCH") (footprint "SWITCH") (libsource (lib "OSA") (part "SWITCH")))
    (comp (ref "S25") (value "SWITCH") (footprint "SWITCH") (libsource (lib "OSA") (part "SWITCH")))
    (comp (ref "S26") (value "SWITCH") (footprint "SWITCH") (libsource (lib "OSA") (part "SWITCH")))
    (comp (ref "S27") (value "SWITCH") (footprint "SWITCH") (libsource (lib "OSA") (part "SWITCH")))
    (comp (ref "S28") (value "SWITCH") (footprint "SWITCH") (libsource (lib "OSA") (part "SWITCH")))
    (comp (ref "S29") (value "SWITCH") (footprint "SWITCH") (libsource (lib "OSA") (part "SWITCH")))
    (comp (ref "S30") (value "SWITCH") (footprint "SWITCH") (libsource (lib "OSA") (part "SWITCH")))
    (comp (ref "S31") (value "SWITCH") (footprint "SWITCH") (libsource (lib "OSA") (part "SWITCH")))
    (comp (ref "S32") (value "SWITCH") (footprint "SWITCH") (libsource (lib "OSA") (part "SWITCH")))
    (comp (ref "S33") (value "SWITCH") (footprint "SWITCH") (libsource (lib "OSA") (part "SWITCH")))
    (comp (ref "S34") (value "SWITCH") (footprint "SWITCH") (libsource (lib "OSA") (part "SWITCH")))
    (comp (ref "S35") (value "SWITCH") (footprint "SWITCH") (libsource (lib "OSA") (part "SWITCH")))
    (comp (ref "S36") (value "SWITCH") (footprint "SWITCH") (libsource (lib "OSA") (part "SWITCH")))
    (comp (ref "S37") (value "SWITCH") (footprint "SWITCH") (libsource (lib "OSA") (part "SWITCH")))
    (comp (ref "S38") (value "SWITCH") (footprint "SWITCH") (libsource (lib "OSA") (part "SWITCH")))
    (comp (ref "S39") (value "SWITCH") (footprint "SWITCH") (libsource (lib "OSA") (part "SWITCH")))
    (comp (ref "S40") (value "SWITCH") (footprint "SWITCH") (libsource (lib "OSA") (part "SWITCH")))
    (comp (ref "S41") (value "SWITCH") (footprint "SWITCH") (libsource (lib "OSA") (part "SWITCH")))
    (comp (ref "S42") (value "SWITCH") (footprint "SWITCH") (libsource (lib "OSA") (part "SWITCH")))
    (comp (ref "S43") (value "SWITCH") (footprint "SWITCH") (libsource (lib "OSA") (part "SWITCH")))
    (comp (ref "S44") (value "SWITCH") (footprint "SWITCH") (libsource (lib "OSA") (part "SWITCH")))
    (comp (ref "S45") (value "SWITCH") (footprint "SWITCH") (libsource (lib "OSA") (part "SWITCH")))
    (comp (ref "S46") (value "SWITCH") (footprint "SWITCH") (libsource (lib "OSA") (part "SWITCH")))
    (comp (ref "S47") (value "SWITCH") (footprint "SWITCH") (libsource (lib "OSA") (part "SWITCH")))
    (comp (ref "S48") (value "SWITCH") (footprint "SWITCH") (libsource (lib "OSA") (part "SWITCH")))
    (comp (ref "S49") (value "SWITCH") (footprint "SWITCH") (libsource (lib "OSA") (part "SWITCH")))
    (comp (ref "S50") (value "SWITCH") (footprint "SWITCH") (libsource (lib "OSA") (part "SWITCH")))
    (comp (ref "S51") (value "SWITCH") (footprint "SWITCH") (libsource (lib "OSA") (part "SWITCH")))
    (comp (ref "S52") (value "SWITCH") (footprint "SWITCH") (libsource (lib "OSA") (part "SWITCH")))
    (comp (ref "S53") (value "SWITCH") (footprint "SWITCH") (libsource (lib "OSA") (part "SWITCH")))
    (comp (ref "S54") (value "SWITCH") (footprint "SWITCH") (libsource (lib "OSA") (part "SWITCH")))
    (comp (ref "S55") (value "SWITCH") (footprint "SWITCH") (libsource (lib "OSA") (part "SWITCH")))
    (comp (ref "S56") (value "SWITCH") (footprint "SWITCH") (libsource (lib "OSA") (part "SWITCH")))
    (comp (ref "S57") (value "SWITCH") (footprint "SWITCH") (libsource (lib "OSA") (part "SWITCH")))
    (comp (ref "S58") (value "SWITCH") (footprint "SWITCH") (libsource (lib "OSA") (part "SWITCH")))
    (comp (ref "S59") (value "SWITCH") (footprint "SWITCH") (libsource (lib "OSA") (part "SWITCH")))
    (comp (ref "S60") (value "SWITCH") (footprint "SWITCH") (libsource (lib "OSA") (part "SWITCH")))
    (comp (ref "S61") (value "SWITCH") (footprint "SWITCH") (libsource (lib "OSA") (part "SWITCH")))
    (comp (ref "S62") (value "SWITCH") (footprint "SWITCH") (libsource (lib "OSA") (part "SWITCH")))
    (comp (ref "S63") (value "SWITCH") (footprint "SWITCH") (libsource (lib "OSA") (part "SWITCH")))
    (comp (ref "S64") (value "SWITCH") (footprint "SWITCH") (libsource (lib "OSA") (part "SWITCH")))
    (comp (ref "S65") (value "SWITCH") (footprint "SWITCH") (libsource (lib "OSA") (part "SWITCH")))
    (comp (ref "S66") (value "SWITCH") (footprint "SWITCH") (libsource (lib "OSA") (part "SWITCH")))
    (comp (ref "U1") (value "WS2811") (footprint "SOP-8") (libsource (lib "OSA") (part "WS2811")))
    (comp (ref "U2") (value "WS2811") (footprint "SOP-8") (libsource (lib "OSA") (part "WS2811")))
    (comp (ref "U3") (value "WS2811") (footprint "SOP-8") (libsource (lib "OSA") (part "WS2811")))
    (comp (ref "U4") (value "WS2811") (footprint "SOP-8") (libsource (lib "OSA") (part "WS2811")))
    (comp (ref "U5") (value "WS2811") (footprint "SOP-8") (libsource (lib "OSA") (part "WS2811")))
  )
  (nets
    (net (code "1") (name "/COL0") (class "Default")
      (node (ref "S1") (pin "2") (pinfunction "2_2") (pintype "passive"))
      (node (ref "S13") (pin "2") (pinfunction "2_2") (pintype "passive"))
      (node (ref "S17") (pin "2") (pinfunction "2_2") (pintype "passive"))
      (node (ref "S5") (pin "2") (pinfunction "2_2") (pintype "passive"))
      (node (ref "S9") (pin "2") (pinfunction "2_2") (pintype "passive"))
    )
    (net (code "2") (name "/COL1") (class "Default")
      (node (ref "S10") (pin "2") (pinfunction "2_2") (pintype "passive"))
      (node (ref "S14") (pin "2") (pinfunction "2_2") (pintype "passive"))
      (node (ref "S18") (pin "2") (pinfunction "2_2") (pintype "passive"))
      (node (ref "S2") (pin "2") (pinfunction "2_2") (pintype "passive"))
      (node (ref "S6") (pin "2") (pinfunction "2_2") (pintype "passive"))
    )
    (net (code "3") (name "/COL2") (class "Default")
      (node (ref "S11") (pin "2") (pinfunction "2_2") (pintype "passive"))
      (node (ref "S15") (pin "2") (pinfunction "2_2") (pintype "passive"))
      (node (ref "S20") (pin "2") (pinfunction "2_2") (pintype "passive"))
      (node (ref "S21") (pin "2") (pinfunction "2_2") (pintype "passive"))
      (node (ref "S3") (pin "2") (pinfunction "2_2") (pintype "passive"))
      (node (ref "S66") (pin "2") (pinfunction "2_2") (pintype "passive"))
      (node (ref "S7") (pin "2") (pinfunction "2_2") (pintype "passive"))
    )
    (net (code "4") (name "/COL3") (class "Default")
      (node (ref "S12") (pin "2") (pinfunction "2_2") (pintype "passive"))
      (node (ref "S16") (pin "2") (pinfunction "2_2") (pintype "passive"))
      (node (ref "S19") (pin "2") (pinfunction "2_2") (pintype "passive"))
      (node (ref "S4") (pin "2") (pinfunction "2_2") (pintype "passive"))
      (node (ref "S8") (pin "2") (pinfunction "2_2") (pintype "passive"))
    )
    (net (code "5") (name "/COL4") (class "Default")
      (node (ref "S22") (pin "2") (pinfunction "2_2") (pintype "passive"))
      (node (ref "S23") (pin "2") (pinfunction "2_2") (pintype "passive"))
      (node (ref "S26") (pin "2") (pinfunction "2_2") (pintype "passive"))
      (node (ref "S29") (pin "2") (pinfunction "2_2") (pintype "passive"))
      (node (ref "S38") (pin "2") (pinfunction "2_2") (pintype "passive"))
      (node (ref "S42") (pin "2") (pinfunction "2_2") (pintype "passive"))
      (node (ref "S46") (pin "2") (pinfunction "2_2") (pintype "passive"))
      (node (ref "S50") (pin "2") (pinfunction "2_2") (pintype "passive"))
    )
    (net (code "6") (name "/COL5") (class "Default")
      (node (ref "S24") (pin "2") (pinfunction "2_2") (pintype "passive"))
      (node (ref "S27") (pin "2") (pinfunction "2_2") (pintype "passive"))
      (node (ref "S30") (pin "2") (pinfunction "2_2") (pintype "passive"))
      (node (ref "S32") (pin "2") (pinfunction "2_2") (pintype "passive"))
      (node (ref "S39") (pin "2") (pinfunction "2_2") (pintype "passive"))
      (node (ref "S43") (pin "2") (pinfunction "2_2") (pintype "passive"))
      (node (ref "S47") (pin "2") (pinfunction "2_2") (pintype "passive"))
      (node (ref "S51") (pin "2") (pinfunction "2_2") (pintype "passive"))
    )
    (net (code "7") (name "/COL6") (class "Default")
      (node (ref "S25") (pin "2") (pinfunction "2_2") (pintype "passive"))
      (node (ref "S28") (pin "2") (pinfunction "2_2") (pintype "passive"))
      (node (ref "S31") (pin "2") (pinfunction "2_2") (pintype "passive"))
      (node (ref "S33") (pin "2") (pinfunction "2_2") (pintype "passive"))
      (node (ref "S40") (pin "2") (pinfunction "2_2") (pintype "passive"))
      (node (ref "S44") (pin "2") (pinfunction "2_2") (pintype "passive"))
      (node (ref "S48") (pin "2") (pinfunction "2_2") (pintype "passive"))
      (node (ref "S52") (pin "2") (pinfunction "2_2") (pintype "passive"))
    )
    (net (code "8") (name "/COL7") (class "Default")
      (node (ref "S34") (pin "2") (pinfunction "2_2") (pintype "passive"))
      (node (ref "S35") (pin "2") (pinfunction "2_2") (pintype "passive"))
      (node (ref "S36") (pin "2") (pinfunction "2_2") (pintype "passive"))
      (node (ref "S37") (pin "2") (pinfunction "2_2") (pintype "passive"))
      (node (ref "S41") (pin "2") (pinfunction "2_2") (pintype "passive"))
      (node (ref "S45") (pin "2") (pinfunction "2_2") (pintype "passive"))
      (node (ref "S49") (pin "2") (pinfunction "2_2") (pintype "passive"))
      (node (ref "S53") (pin "2") (pinfunction "2_2") (pintype "passive"))
    )
    (net (code "9") (name "/COL8") (class "Default")
      (node (ref "P2") (pin "7") (pinfunction "7_7") (pintype "passive"))
      (node (ref "S54") (pin "2") (pinfunction "2_2") (pintype "passive"))
      (node (ref "S55") (pin "2") (pinfunction "2_2") (pintype "passive"))
      (node (ref "S56") (pin "2") (pinfunction "2_2") (pintype "passive"))
      (node (ref "S57") (pin "2") (pinfunction "2_2") (pintype "passive"))
    )
    (net (code "10") (name "/COL9") (class "Default")
      (node (ref "P2") (pin "6") (pinfunction "6_6") (pintype "passive"))
      (node (ref "S58") (pin "2") (pinfunction "2_2") (pintype "passive"))
      (node (ref "S59") (pin "2") (pinfunction "2_2") (pintype "passive"))
      (node (ref "S60") (pin "2") (pinfunction "2_2") (pintype "passive"))
      (node (ref "S61") (pin "2") (pinfunction "2_2") (pintype "passive"))
    )
    (net (code "11") (name "/COL10") (class "Default")
      (node (ref "P1") (pin "5") (pinfunction "5_5") (pintype "passive"))
      (node (ref "S62") (pin "2") (pinfunction "2_2") (pintype "passive"))
      (node (ref "S63") (pin "2") (pinfunction "2_2") (pintype "passive"))
      (node (ref "S64") (pin "2") (pinfunction "2_2") (pintype "passive"))
      (node (ref "S65") (pin "2") (pinfunction "2_2") (pintype "passive"))
    )
    (net (code "12") (name "/ENC_A") (class "Default")
      (node (ref "E1") (pin "8") (pinfunction "8_8") (pintype "passive"))
      (node (ref "R9") (pin "2") (pinfunction "2_2") (pintype "passive"))
    )
    (net (code "13") (name "/ENC_B") (class "Default")
      (node (ref "E1") (pin "6") (pinfunction "6_6") (pintype "passive"))
      (node (ref "R7") (pin "1") (pinfunction "1_1") (pintype "passive"))
    )
    (net (code "14") (name "/LED13") (class "Default")
      (node (ref "P2") (pin "2") (pinfunction "2_2") (pintype "passive"))
      (node (ref "U5") (pin "1") (pinfunction "OUTR_1") (pintype "passive"))
    )
    (net (code "15") (name "/LED14") (class "Default")
      (node (ref "P2") (pin "3") (pinfunction "3_3") (pintype "passive"))
      (node (ref "U5") (pin "2") (pinfunction "OUTG_2") (pintype "passive"))
    )
    (net (code "16") (name "/LEDDATA") (class "Default")
      (node (ref "R1") (pin "2") (pinfunction "2_2") (pintype "passive"))
    )
    (net (code "17") (name "/LOCK") (class "Default")
      (node (ref "P2") (pin "15") (pinfunction "15_15") (pintype "passive"))
    )
    (net (code "18") (name "/ROW0") (class "Default")
      (node (ref "D1") (pin "3") (pinfunction "COMAC_3") (pintype "passive"))
      (node (ref "D10") (pin "3") (pinfunction "COMAC_3") (pintype "passive"))
      (node (ref "D11") (pin "3") (pinfunction "COMAC_3") (pintype "passive"))
      (node (ref "D2") (pin "3") (pinfunction "COMAC_3") (pintype "passive"))
      (node (ref "D3") (pin "3") (pinfunction "COMAC_3") (pintype "passive"))
      (node (ref "D4") (pin "3") (pinfunction "COMAC_3") (pintype "passive"))
      (node (ref "D5") (pin "3") (pinfunction "COMAC_3") (pintype "passive"))
      (node (ref "D6") (pin "3") (pinfunction "COMAC_3") (pintype "passive"))
      (node (ref "D7") (pin "3") (pinfunction "COMAC_3") (pintype "passive"))
      (node (ref "D8") (pin "3") (pinfunction "COMAC_3") (pintype "passive"))
      (node (ref "D9") (pin "3") (pinfunction "COMAC_3") (pintype "passive"))
    )
    (net (code "19") (name "/ROW1") (class "Default")
      (node (ref "D12") (pin "3") (pinfunction "COMAC_3") (pintype "passive"))
      (node (ref "D13") (pin "3") (pinfunction "COMAC_3") (pintype "passive"))
      (node (ref "D14") (pin "3") (pinfunction "COMAC_3") (pintype "passive"))
      (node (ref "D15") (pin "3") (pinfunction "COMAC_3") (pintype "passive"))
      (node (ref "D16") (pin "3") (pinfunction "COMAC_3") (pintype "passive"))
      (node (ref "D17") (pin "3") (pinfunction "COMAC_3") (pintype "passive"))
      (node (ref "D18") (pin "3") (pinfunction "COMAC_3") (pintype "passive"))
      (node (ref "D19") (pin "3") (pinfunction "COMAC_3") (pintype "passive"))
      (node (ref "D20") (pin "3") (pinfunction "COMAC_3") (pintype "passive"))
      (node (ref "D21") (pin "3") (pinfunction "COMAC_3") (pintype "passive"))
      (node (ref "D22") (pin "3") (pinfunction "COMAC_3") (pintype "passive"))
    )
    (net (code "20") (name "/ROW2") (class "Default")
      (node (ref "D23") (pin "3") (pinfunction "COMAC_3") (pintype "passive"))
      (node (ref "D24") (pin "3") (pinfunction "COMAC_3") (pintype "passive"))
      (node (ref "D25") (pin "3") (pinfunction "COMAC_3") (pintype "passive"))
      (node (ref "D26") (pin "3") (pinfunction "COMAC_3") (pintype "passive"))
      (node (ref "D27") (pin "3") (pinfunction "COMAC_3") (pintype "passive"))
      (node (ref "D28") (pin "3") (pinfunction "COMAC_3") (pintype "passive"))
      (node (ref "D29") (pin "3") (pinfunction "COMAC_3") (pintype "passive"))
      (node (ref "D30") (pin "3") (pinfunction "COMAC_3") (pintype "passive"))
      (node (ref "D31") (pin "3") (pinfunction "COMAC_3") (pintype "passive"))
      (node (ref "D32") (pin "3") (pinfunction "COMAC_3") (pintype "passive"))
      (node (ref "D33") (pin "3") (pinfunction "COMAC_3") (pintype "passive"))
    )
    (net (code "21") (name "/ROW3") (class "Default")
      (node (ref "D34") (pin "3") (pinfunction "COMAC_3") (pintype "passive"))
      (node (ref "D35") (pin "3") (pinfunction "COMAC_3") (pintype "passive"))
      (node (ref "D36") (pin "3") (pinfunction "COMAC_3") (pintype "passive"))
      (node (ref "D37") (pin "3") (pinfunction "COMAC_3") (pintype "passive"))
      (node (ref "D38") (pin "3") (pinfunction "COMAC_3") (pintype "passive"))
      (node (ref "D39") (pin "3") (pinfunction "COMAC_3") (pintype "passive"))
      (node (ref "D40") (pin "3") (pinfunction "COMAC_3") (pintype "passive"))
      (node (ref "D41") (pin "3") (pinfunction "COMAC_3") (pintype "passive"))
      (node (ref "D42") (pin "3") (pinfunction "COMAC_3") (pintype "passive"))
      (node (ref "D43") (pin "3") (pinfunction "COMAC_3") (pintype "passive"))
      (node (ref "D44") (pin "3") (pinfunction "COMAC_3") (pintype "passive"))
    )
    (net (code "22") (name "/ROW4") (class "Default")
      (node (ref "D45") (pin "3") (pinfunction "COMAC_3") (pintype "passive"))
      (node (ref "D46") (pin "3") (pinfunction "COMAC_3") (pintype "passive"))
      (node (ref "D47") (pin "3") (pinfunction "COMAC_3") (pintype "passive"))
      (node (ref "D48") (pin "3") (pinfunction "COMAC_3") (pintype "passive"))
      (node (ref "D49") (pin "3") (pinfunction "COMAC_3") (pintype "passive"))
      (node (ref "D68") (pin "3") (pinfunction "COMAC_3") (pintype "passive"))
      (node (ref "P2") (pin "9") (pinfunction "9_9") (pintype "passive"))
    )
    (net (code "23") (name "/ROW5") (class "Default")
      (node (ref "D50") (pin "3") (pinfunction "COMAC_3") (pintype "passive"))
      (node (ref "D51") (pin "3") (pinfunction "COMAC_3") (pintype "passive"))
      (node (ref "D52") (pin "3") (pinfunction "COMAC_3") (pintype "passive"))
      (node (ref "D53") (pin "3") (pinfunction "COMAC_3") (pintype "passive"))
      (node (ref "D54") (pin "3") (pinfunction "COMAC_3") (pintype "passive"))
      (node (ref "D67") (pin "3") (pinfunction "COMAC_3") (pintype "passive"))
      (node (ref "P2") (pin "11") (pinfunction "11_11") (pintype "passive"))
    )
    (net (code "24") (name "/ROW6") (class "Default")
      (node (ref "D55") (pin "3") (pinfunction "COMAC_3") (pintype "passive"))
      (node (ref "D56") (pin "3") (pinfunction "COMAC_3") (pintype "passive"))
      (node (ref "D57") (pin "3") (pinfunction "COMAC_3") (pintype "passive"))
      (node (ref "D58") (pin "3") (pinfunction "COMAC_3") (pintype "passive"))
      (node (ref "D59") (pin "3") (pinfunction "COMAC_3") (pintype "passive"))
      (node (ref "D60") (pin "3") (pinfunction "COMAC_3") (pintype "passive"))
      (node (ref "D61") (pin "3") (pinfunction "COMAC_3") (pintype "passive"))
      (node (ref "P2") (pin "8") (pinfunction "8_8") (pintype "passive"))
    )
    (net (code "25") (name "/ROW7") (class "Default")
      (node (ref "D62") (pin "3") (pinfunction "COMAC_3") (pintype "passive"))
      (node (ref "D63") (pin "3") (pinfunction "COMAC_3") (pintype "passive"))
      (node (ref "D64") (pin "3") (pinfunction "COMAC_3") (pintype "passive"))
      (node (ref "D65") (pin "3") (pinfunction "COMAC_3") (pintype "passive"))
      (node (ref "D66") (pin "3") (pinfunction "COMAC_3") (pintype "passive"))
      (node (ref "P2") (pin "10") (pinfunction "10_10") (pintype "passive"))
    )
    (net (code "26") (name "5V") (class "Default")
      (node (ref "E1") (pin "5") (pinfunction "5_5") (pintype "passive"))
      (node (ref "E1") (pin "7") (pinfunction "7_7") (pintype "passive"))
      (node (ref "LD1") (pin "2") (pinfunction "A_2") (pintype "passive"))
      (node (ref "LD10") (pin "2") (pinfunction "A_2") (pintype "passive"))
      (node (ref "LD11") (pin "2") (pinfunction "A_2") (pintype "passive"))
      (node (ref "LD12") (pin "2") (pinfunction "A_2") (pintype "passive"))
      (node (ref "LD2") (pin "2") (pinfunction "A_2") (pintype "passive"))
      (node (ref "LD3") (pin "2") (pinfunction "A_2") (pintype "passive"))
      (node (ref "LD4") (pin "2") (pinfunction "A_2") (pintype "passive"))
      (node (ref "LD5") (pin "2") (pinfunction "A_2") (pintype "passive"))
      (node (ref "LD6") (pin "2") (pinfunction "A_2") (pintype "passive"))
      (node (ref "LD7") (pin "2") (pinfunction "A_2") (pintype "passive"))
      (node (ref "LD8") (pin "2") (pinfunction "A_2") (pintype "passive"))
      (node (ref "LD9") (pin "2") (pinfunction "A_2") (pintype "passive"))
      (node (ref "P2") (pin "1") (pinfunction "1_1") (pintype "passive"))
      (node (ref "R2") (pin "2") (pinfunction "2_2") (pintype "passive"))
      (node (ref "R8") (pin "1") (pinfunction "1_1") (pintype "passive"))
    )
    (net (code "27") (name "GND") (class "Default")
      (node (ref "E1") (pin "4") (pinfunction "4_4") (pintype "passive"))
      (node (ref "P2") (pin "13") (pinfunction "13_13") (pintype "passive"))
      (node (ref "R7") (pin "2") (pinfunction "2_2") (pintype "passive"))
      (node (ref "R9") (pin "1") (pinfunction "1_1") (pintype "passive"))
      (node (ref "U1") (pin "4") (pinfunction "GND_4") (pintype "passive"))
      (node (ref "U2") (pin "4") (pinfunction "GND_4") (pintype "passive"))
      (node (ref "U3") (pin "4") (pinfunction "GND_4") (pintype "passive"))
      (node (ref "U4") (pin "4") (pinfunction "GND_4") (pintype "passive"))
      (node (ref "U5") (pin "4") (pinfunction "GND_4") (pintype "passive"))
    )
    (net (code "28") (name "Net-(D1A-A)") (class "Default")
      (node (ref "D1") (pin "1") (pinfunction "A_1") (pintype "passive"))
      (node (ref "S1") (pin "1") (pinfunction "1_1") (pintype "passive"))
    )
    (net (code "29") (name "Net-(D2A-A)") (class "Default")
      (node (ref "D2") (pin "1") (pinfunction "A_1") (pintype "passive"))
      (node (ref "S2") (pin "1") (pinfunction "1_1") (pintype "passive"))
    )
    (net (code "30") (name "Net-(D3A-A)") (class "Default")
      (node (ref "D3") (pin "1") (pinfunction "A_1") (pintype "passive"))
      (node (ref "S3") (pin "1") (pinfunction "1_1") (pintype "passive"))
    )
    (net (code "31") (name "Net-(D4A-A)") (class "Default")
      (node (ref "D4") (pin "1") (pinfunction "A_1") (pintype "passive"))
      (node (ref "S4") (pin "1") (pinfunction "1_1") (pintype "passive"))
    )
    (net (code "32") (name "Net-(D5A-A)") (class "Default")
      (node (ref "D5") (pin "1") (pinfunction "A_1") (pintype "passive"))
      (node (ref "S38") (pin "1") (pinfunction "1_1") (pintype "passive"))
    )
    (net (code "33") (name "Net-(D6A-A)") (class "Default")
      (node (ref "D6") (pin "1") (pinfunction "A_1") (pintype "passive"))
      (node (ref "S39") (pin "1") (pinfunction "1_1") (pintype "passive"))
    )
    (net (code "34") (name "Net-(D7A-A)") (class "Default")
      (node (ref "D7") (pin "1") (pinfunction "A_1") (pintype "passive"))
      (node (ref "S40") (pin "1") (pinfunction "1_1") (pintype "passive"))
    )
    (net (code "35") (name "Net-(D8A-A)") (class "Default")
      (node (ref "D8") (pin "1") (pinfunction "A_1") (pintype "passive"))
      (node (ref "S41") (pin "1") (pinfunction "1_1") (pintype "passive"))
    )
    (net (code "36") (name "Net-(D9A-A)") (class "Default")
      (node (ref "D9") (pin "1") (pinfunction "A_1") (pintype "passive"))
      (node (ref "S54") (pin "1") (pinfunction "1_1") (pintype "passive"))
    )
    (net (code "37") (name "Net-(D10A-A)") (class "Default")
      (node (ref "D10") (pin "1") (pinfunction "A_1") (pintype "passive"))
      (node (ref "S58") (pin "1") (pinfunction "1_1") (pintype "passive"))
    )
    (net (code "38") (name "Net-(D11A-A)") (class "Default")
      (node (ref "D11") (pin "1") (pinfunction "A_1") (pintype "passive"))
      (node (ref "S62") (pin "1") (pinfunction "1_1") (pintype "passive"))
    )
    (net (code "39") (name "Net-(D12A-A)") (class "Default")
      (node (ref "D12") (pin "1") (pinfunction "A_1") (pintype "passive"))
      (node (ref "S5") (pin "1") (pinfunction "1_1") (pintype "passive"))
    )
    (net (code "40") (name "Net-(D13A-A)") (class "Default")
      (node (ref "D13") (pin "1") (pinfunction "A_1") (pintype "passive"))
      (node (ref "S6") (pin "1") (pinfunction "1_1") (pintype "passive"))
    )
    (net (code "41") (name "Net-(D14A-A)") (class "Default")
      (node (ref "D14") (pin "1") (pinfunction "A_1") (pintype "passive"))
      (node (ref "S7") (pin "1") (pinfunction "1_1") (pintype "passive"))
    )
    (net (code "42") (name "Net-(D15A-A)") (class "Default")
      (node (ref "D15") (pin "1") (pinfunction "A_1") (pintype "passive"))
      (node (ref "S8") (pin "1") (pinfunction "1_1") (pintype "passive"))
    )
    (net (code "43") (name "Net-(D16A-A)") (class "Default")
      (node (ref "D16") (pin "1") (pinfunction "A_1") (pintype "passive"))
      (node (ref "S42") (pin "1") (pinfunction "1_1") (pintype "passive"))
    )
    (net (code "44") (name "Net-(D17A-A)") (class "Default")
      (node (ref "D17") (pin "1") (pinfunction "A_1") (pintype "passive"))
      (node (ref "S43") (pin "1") (pinfunction "1_1") (pintype "passive"))
    )
    (net (code "45") (name "Net-(D18A-A)") (class "Default")
      (node (ref "D18") (pin "1") (pinfunction "A_1") (pintype "passive"))
      (node (ref "S44") (pin "1") (pinfunction "1_1") (pintype "passive"))
    )
    (net (code "46") (name "Net-(D19A-A)") (class "Default")
      (node (ref "D19") (pin "1") (pinfunction "A_1") (pintype "passive"))
      (node (ref "S45") (pin "1") (pinfunction "1_1") (pintype "passive"))
    )
    (net (code "47") (name "Net-(D20A-A)") (class "Default")
      (node (ref "D20") (pin "1") (pinfunction "A_1") (pintype "passive"))
      (node (ref "S55") (pin "1") (pinfunction "1_1") (pintype "passive"))
    )
    (net (code "48") (name "Net-(D21A-A)") (class "Default")
      (node (ref "D21") (pin "1") (pinfunction "A_1") (pintype "passive"))
      (node (ref "S59") (pin "1") (pinfunction "1_1") (pintype "passive"))
    )
    (net (code "49") (name "Net-(D22A-A)") (class "Default")
      (node (ref "D22") (pin "1") (pinfunction "A_1") (pintype "passive"))
      (node (ref "S63") (pin "1") (pinfunction "1_1") (pintype "passive"))
    )
    (net (code "50") (name "Net-(D23A-A)") (class "Default")
      (node (ref "D23") (pin "1") (pinfunction "A_1") (pintype "passive"))
      (node (ref "S9") (pin "1") (pinfunction "1_1") (pintype "passive"))
    )
    (net (code "51") (name "Net-(D24A-A)") (class "Default")
      (node (ref "D24") (pin "1") (pinfunction "A_1") (pintype "passive"))
      (node (ref "S10") (pin "1") (pinfunction "1_1") (pintype "passive"))
    )
    (net (code "52") (name "Net-(D25A-A)") (class "Default")
      (node (ref "D25") (pin "1") (pinfunction "A_1") (pintype "passive"))
      (node (ref "S11") (pin "1") (pinfunction "1_1") (pintype "passive"))
    )
    (net (code "53") (name "Net-(D26A-A)") (class "Default")
      (node (ref "D26") (pin "1") (pinfunction "A_1") (pintype "passive"))
      (node (ref "S12") (pin "1") (pinfunction "1_1") (pintype "passive"))
    )
    (net (code "54") (name "Net-(D27A-A)") (class "Default")
      (node (ref "D27") (pin "1") (pinfunction "A_1") (pintype "passive"))
      (node (ref "S46") (pin "1") (pinfunction "1_1") (pintype "passive"))
    )
    (net (code "55") (name "Net-(D28A-A)") (class "Default")
      (node (ref "D28") (pin "1") (pinfunction "A_1") (pintype "passive"))
      (node (ref "S47") (pin "1") (pinfunction "1_1") (pintype "passive"))
    )
    (net (code "56") (name "Net-(D29A-A)") (class "Default")
      (node (ref "D29") (pin "1") (pinfunction "A_1") (pintype "passive"))
      (node (ref "S48") (pin "1") (pinfunction "1_1") (pintype "passive"))
    )
    (net (code "57") (name "Net-(D30A-A)") (class "Default")
      (node (ref "D30") (pin "1") (pinfunction "A_1") (pintype "passive"))
      (node (ref "S49") (pin "1") (pinfunction "1_1") (pintype "passive"))
    )
    (net (code "58") (name "Net-(D31A-A)") (class "Default")
      (node (ref "D31") (pin "1") (pinfunction "A_1") (pintype "passive"))
      (node (ref "S56") (pin "1") (pinfunction "1_1") (pintype "passive"))
    )
    (net (code "59") (name "Net-(D32A-A)") (class "Default")
      (node (ref "D32") (pin "1") (pinfunction "A_1") (pintype "passive"))
      (node (ref "S60") (pin "1") (pinfunction "1_1") (pintype "passive"))
    )
    (net (code "60") (name "Net-(D33A-A)") (class "Default")
      (node (ref "D33") (pin "1") (pinfunction "A_1") (pintype "passive"))
      (node (ref "S64") (pin "1") (pinfunction "1_1") (pintype "passive"))
    )
    (net (code "61") (name "Net-(D34A-A)") (class "Default")
      (node (ref "D34") (pin "1") (pinfunction "A_1") (pintype "passive"))
      (node (ref "S13") (pin "1") (pinfunction "1_1") (pintype "passive"))
    )
    (net (code "62") (name "Net-(D35A-A)") (class "Default")
      (node (ref "D35") (pin "1") (pinfunction "A_1") (pintype "passive"))
      (node (ref "S14") (pin "1") (pinfunction "1_1") (pintype "passive"))
    )
    (net (code "63") (name "Net-(D36A-A)") (class "Default")
      (node (ref "D36") (pin "1") (pinfunction "A_1") (pintype "passive"))
      (node (ref "S15") (pin "1") (pinfunction "1_1") (pintype "passive"))
    )
    (net (code "64") (name "Net-(D37A-A)") (class "Default")
      (node (ref "D37") (pin "1") (pinfunction "A_1") (pintype "passive"))
      (node (ref "S16") (pin "1") (pinfunction "1_1") (pintype "passive"))
    )
    (net (code "65") (name "Net-(D38A-A)") (class "Default")
      (node (ref "D38") (pin "1") (pinfunction "A_1") (pintype "passive"))
      (node (ref "S50") (pin "1") (pinfunction "1_1") (pintype "passive"))
    )
    (net (code "66") (name "Net-(D39A-A)") (class "Default")
      (node (ref "D39") (pin "1") (pinfunction "A_1") (pintype "passive"))
      (node (ref "S51") (pin "1") (pinfunction "1_1") (pintype "passive"))
    )
    (net (code "67") (name "Net-(D40A-A)") (class "Default")
      (node (ref "D40") (pin "1") (pinfunction "A_1") (pintype "passive"))
      (node (ref "S52") (pin "1") (pinfunction "1_1") (pintype "passive"))
    )
    (net (code "68") (name "Net-(D41A-A)") (class "Default")
      (node (ref "D41") (pin "1") (pinfunction "A_1") (pintype "passive"))
      (node (ref "S53") (pin "1") (pinfunction "1_1") (pintype "passive"))
    )
    (net (code "69") (name "Net-(D42A-A)") (class "Default")
      (node (ref "D42") (pin "1") (pinfunction "A_1") (pintype "passive"))
      (node (ref "S57") (pin "1") (pinfunction "1_1") (pintype "passive"))
    )
    (net (code "70") (name "Net-(D43A-A)") (class "Default")
      (node (ref "D43") (pin "1") (pinfunction "A_1") (pintype "passive"))
      (node (ref "S61") (pin "1") (pinfunction "1_1") (pintype "passive"))
    )
    (net (code "71") (name "Net-(D44A-A)") (class "Default")
      (node (ref "D44") (pin "1") (pinfunction "A_1") (pintype "passive"))
      (node (ref "S65") (pin "1") (pinfunction "1_1") (pintype "passive"))
    )
    (net (code "72") (name "Net-(D45A-A)") (class "Default")
      (node (ref "D45") (pin "1") (pinfunction "A_1") (pintype "passive"))
      (node (ref "S17") (pin "1") (pinfunction "1_1") (pintype "passive"))
    )
    (net (code "73") (name "Net-(D46A-A)") (class "Default")
      (node (ref "D46") (pin "1") (pinfunction "A_1") (pintype "passive"))
      (node (ref "S29") (pin "1") (pinfunction "1_1") (pintype "passive"))
    )
    (net (code "74") (name "Net-(D47A-A)") (class "Default")
      (node (ref "D47") (pin "1") (pinfunction "A_1") (pintype "passive"))
      (node (ref "S30") (pin "1") (pinfunction "1_1") (pintype "passive"))
    )
    (net (code "75") (name "Net-(D48A-A)") (class "Default")
      (node (ref "D48") (pin "1") (pinfunction "A_1") (pintype "passive"))
      (node (ref "S31") (pin "1") (pinfunction "1_1") (pintype "passive"))
    )
    (net (code "76") (name "Net-(D49A-A)") (class "Default")
      (node (ref "D49") (pin "1") (pinfunction "A_1") (pintype "passive"))
      (node (ref "S37") (pin "1") (pinfunction "1_1") (pintype "passive"))
    )
    (net (code "77") (name "Net-(D50A-A)") (class "Default")
      (node (ref "D50") (pin "1") (pinfunction "A_1") (pintype "passive"))
      (node (ref "S20") (pin "1") (pinfunction "1_1") (pintype "passive"))
    )
    (net (code "78") (name "Net-(D51A-A)") (class "Default")
      (node (ref "D51") (pin "1") (pinfunction "A_1") (pintype "passive"))
      (node (ref "S26") (pin "1") (pinfunction "1_1") (pintype "passive"))
    )
    (net (code "79") (name "Net-(D52A-A)") (class "Default")
      (node (ref "D52") (pin "1") (pinfunction "A_1") (pintype "passive"))
      (node (ref "S27") (pin "1") (pinfunction "1_1") (pintype "passive"))
    )
    (net (code "80") (name "Net-(D53A-A)") (class "Default")
      (node (ref "D53") (pin "1") (pinfunction "A_1") (pintype "passive"))
      (node (ref "S28") (pin "1") (pinfunction "1_1") (pintype "passive"))
    )
    (net (code "81") (name "Net-(D54A-A)") (class "Default")
      (node (ref "D54") (pin "1") (pinfunction "A_1") (pintype "passive"))
      (node (ref "S36") (pin "1") (pinfunction "1_1") (pintype "passive"))
    )
    (net (code "82") (name "Net-(D55A-A)") (class "Default")
      (node (ref "D55") (pin "1") (pinfunction "A_1") (pintype "passive"))
      (node (ref "S18") (pin "1") (pinfunction "1_1") (pintype "passive"))
    )
    (net (code "83") (name "Net-(D56A-A)") (class "Default")
      (node (ref "D56") (pin "1") (pinfunction "A_1") (pintype "passive"))
      (node (ref "S66") (pin "1") (pinfunction "1_1") (pintype "passive"))
    )
    (net (code "84") (name "Net-(D57A-A)") (class "Default")
      (node (ref "D57") (pin "1") (pinfunction "A_1") (pintype "passive"))
      (node (ref "S19") (pin "1") (pinfunction "1_1") (pintype "passive"))
    )
    (net (code "85") (name "Net-(D58A-A)") (class "Default")
      (node (ref "D58") (pin "1") (pinfunction "A_1") (pintype "passive"))
      (node (ref "S23") (pin "1") (pinfunction "1_1") (pintype "passive"))
    )
    (net (code "86") (name "Net-(D59A-A)") (class "Default")
      (node (ref "D59") (pin "1") (pinfunction "A_1") (pintype "passive"))
      (node (ref "S24") (pin "1") (pinfunction "1_1") (pintype "passive"))
    )
    (net (code "87") (name "Net-(D60A-A)") (class "Default")
      (node (ref "D60") (pin "1") (pinfunction "A_1") (pintype "passive"))
      (node (ref "S25") (pin "1") (pinfunction "1_1") (pintype "passive"))
    )
    (net (code "88") (name "Net-(D61A-A)") (class "Default")
      (node (ref "D61") (pin "1") (pinfunction "A_1") (pintype "passive"))
      (node (ref "S35") (pin "1") (pinfunction "1_1") (pintype "passive"))
    )
    (net (code "89") (name "Net-(D62A-A)") (class "Default")
      (node (ref "D62") (pin "1") (pinfunction "A_1") (pintype "passive"))
      (node (ref "S21") (pin "1") (pinfunction "1_1") (pintype "passive"))
    )
    (net (code "90") (name "Net-(D63A-A)") (class "Default")
      (node (ref "D63") (pin "1") (pinfunction "A_1") (pintype "passive"))
      (node (ref "S22") (pin "1") (pinfunction "1_1") (pintype "passive"))
    )
    (net (code "91") (name "Net-(D64A-A)") (class "Default")
      (node (ref "D64") (pin "1") (pinfunction "A_1") (pintype "passive"))
      (node (ref "S32") (pin "1") (pinfunction "1_1") (pintype "passive"))
    )
    (net (code "92") (name "Net-(D65A-A)") (class "Default")
      (node (ref "D65") (pin "1") (pinfunction "A_1") (pintype "passive"))
      (node (ref "S33") (pin "1") (pinfunction "1_1") (pintype "passive"))
    )
    (net (code "93") (name "Net-(D66A-A)") (class "Default")
      (node (ref "D66") (pin "1") (pinfunction "A_1") (pintype "passive"))
      (node (ref "S34") (pin "1") (pinfunction "1_1") (pintype "passive"))
    )
    (net (code "94") (name "Net-(D67A-A)") (class "Default")
      (node (ref "D67") (pin "1") (pinfunction "A_1") (pintype "passive"))
      (node (ref "P1") (pin "3") (pinfunction "3_3") (pintype "passive"))
    )
    (net (code "95") (name "Net-(D68A-A)") (class "Default")
      (node (ref "D68") (pin "1") (pinfunction "A_1") (pintype "passive"))
      (node (ref "P1") (pin "4") (pinfunction "4_4") (pintype "passive"))
    )
    (net (code "96") (name "Net-(E1-Pad1)") (class "Default")
      (node (ref "E1") (pin "1") (pinfunction "1_1") (pintype "passive"))
      (node (ref "R8") (pin "2") (pinfunction "2_2") (pintype "passive"))
    )
    (net (code "97") (name "Net-(E1-Pad2)") (class "Default")
      (node (ref "E1") (pin "2") (pinfunction "2_2") (pintype "passive"))
      (node (ref "E1") (pin "3") (pinfunction "3_3") (pintype "passive"))
    )
    (net (code "98") (name "Net-(LD1-C)") (class "Default")
      (node (ref "LD1") (pin "1") (pinfunction "C_1") (pintype "passive"))
      (node (ref "U1") (pin "1") (pinfunction "OUTR_1") (pintype "passive"))
    )
    (net (code "99") (name "Net-(LD2-C)") (class "Default")
      (node (ref "LD2") (pin "1") (pinfunction "C_1") (pintype "passive"))
      (node (ref "U1") (pin "2") (pinfunction "OUTG_2") (pintype "passive"))
    )
    (net (code "100") (name "Net-(LD3-C)") (class "Default")
      (node (ref "LD3") (pin "1") (pinfunction "C_1") (pintype "passive"))
      (node (ref "U1") (pin "3") (pinfunction "OUTB_3") (pintype "passive"))
    )
    (net (code "101") (name "Net-(LD4-C)") (class "Default")
      (node (ref "LD4") (pin "1") (pinfunction "C_1") (pintype "passive"))
      (node (ref "U2") (pin "1") (pinfunction "OUTR_1") (pintype "passive"))
    )
    (net (code "102") (name "Net-(LD5-C)") (class "Default")
      (node (ref "LD5") (pin "1") (pinfunction "C_1") (pintype "passive"))
      (node (ref "U2") (pin "2") (pinfunction "OUTG_2") (pintype "passive"))
    )
    (net (code "103") (name "Net-(LD6-C)") (class "Default")
      (node (ref "LD6") (pin "1") (pinfunction "C_1") (pintype "passive"))
      (node (ref "U2") (pin "3") (pinfunction "OUTB_3") (pintype "passive"))
    )
    (net (code "104") (name "Net-(LD7-C)") (class "Default")
      (node (ref "LD7") (pin "1") (pinfunction "C_1") (pintype "passive"))
      (node (ref "U3") (pin "1") (pinfunction "OUTR_1") (pintype "passive"))
    )
    (net (code "105") (name "Net-(LD8-C)") (class "Default")
      (node (ref "LD8") (pin "1") (pinfunction "C_1") (pintype "passive"))
      (node (ref "U3") (pin "2") (pinfunction "OUTG_2") (pintype "passive"))
    )
    (net (code "106") (name "Net-(LD9-C)") (class "Default")
      (node (ref "LD9") (pin "1") (pinfunction "C_1") (pintype "passive"))
      (node (ref "U3") (pin "3") (pinfunction "OUTB_3") (pintype "passive"))
    )
    (net (code "107") (name "Net-(LD10-C)") (class "Default")
      (node (ref "LD10") (pin "1") (pinfunction "C_1") (pintype "passive"))
      (node (ref "U4") (pin "1") (pinfunction "OUTR_1") (pintype "passive"))
    )
    (net (code "108") (name "Net-(LD11-C)") (class "Default")
      (node (ref "LD11") (pin "1") (pinfunction "C_1") (pintype "passive"))
      (node (ref "U4") (pin "2") (pinfunction "OUTG_2") (pintype "passive"))
    )
    (net (code "109") (name "Net-(LD12-C)") (class "Default")
      (node (ref "LD12") (pin "1") (pinfunction "C_1") (pintype "passive"))
      (node (ref "U4") (pin "3") (pinfunction "OUTB_3") (pintype "passive"))
    )
    (net (code "110") (name "Net-(U1-DIN)") (class "Default")
      (node (ref "R1") (pin "1") (pinfunction "1_1") (pintype "passive"))
      (node (ref "U1") (pin "6") (pinfunction "DIN_6") (pintype "passive"))
    )
    (net (code "111") (name "Net-(U1-DO)") (class "Default")
      (node (ref "R3") (pin "2") (pinfunction "2_2") (pintype "passive"))
      (node (ref "U1") (pin "5") (pinfunction "DO_5") (pintype "passive"))
    )
    (net (code "112") (name "Net-(U1-VDD)") (class "Default")
      (node (ref "R2") (pin "1") (pinfunction "1_1") (pintype "passive"))
      (node (ref "U1") (pin "8") (pinfunction "VDD_8") (pintype "passive"))
      (node (ref "U2") (pin "8") (pinfunction "VDD_8") (pintype "passive"))
      (node (ref "U3") (pin "8") (pinfunction "VDD_8") (pintype "passive"))
      (node (ref "U4") (pin "8") (pinfunction "VDD_8") (pintype "passive"))
      (node (ref "U5") (pin "8") (pinfunction "VDD_8") (pintype "passive"))
    )
    (net (code "113") (name "Net-(U2-DIN)") (class "Default")
      (node (ref "R3") (pin "1") (pinfunction "1_1") (pintype "passive"))
      (node (ref "U2") (pin "6") (pinfunction "DIN_6") (pintype "passive"))
    )
    (net (code "114") (name "Net-(U2-DO)") (class "Default")
      (node (ref "R4") (pin "2") (pinfunction "2_2") (pintype "passive"))
      (node (ref "U2") (pin "5") (pinfunction "DO_5") (pintype "passive"))
    )
    (net (code "115") (name "Net-(U3-DIN)") (class "Default")
      (node (ref "R4") (pin "1") (pinfunction "1_1") (pintype "passive"))
      (node (ref "U3") (pin "6") (pinfunction "DIN_6") (pintype "passive"))
    )
    (net (code "116") (name "Net-(U3-DO)") (class "Default")
      (node (ref "R5") (pin "2") (pinfunction "2_2") (pintype "passive"))
      (node (ref "U3") (pin "5") (pinfunction "DO_5") (pintype "passive"))
    )
    (net (code "117") (name "Net-(U4-DIN)") (class "Default")
      (node (ref "R5") (pin "1") (pinfunction "1_1") (pintype "passive"))
      (node (ref "U4") (pin "6") (pinfunction "DIN_6") (pintype "passive"))
    )
    (net (code "118") (name "Net-(U4-DO)") (class "Default")
      (node (ref "R6") (pin "2") (pinfunction "2_2") (pintype "passive"))
      (node (ref "U4") (pin "5") (pinfunction "DO_5") (pintype "passive"))
    )
    (net (code "119") (name "Net-(U5-DIN)") (class "Default")
      (node (ref "R6") (pin "1") (pinfunction "1_1") (pintype "passive"))
      (node (ref "U5") (pin "6") (pinfunction "DIN_6") (pintype "passive"))
    )
    (net (code "120") (name "VCC") (class "Default")
      (node (ref "P2") (pin "14") (pinfunction "14_14") (pintype "passive"))
    )
    (net (code "121") (name "unconnected-(P1-Pad1)") (class "Default")
      (node (ref "P1") (pin "1") (pinfunction "1_1") (pintype "passive"))
    )
    (net (code "122") (name "unconnected-(P1-Pad2)") (class "Default")
      (node (ref "P1") (pin "2") (pinfunction "2_2") (pintype "passive"))
    )
    (net (code "123") (name "unconnected-(P1-Pad6)") (class "Default")
      (node (ref "P1") (pin "6") (pinfunction "6_6") (pintype "passive"))
    )
    (net (code "124") (name "unconnected-(P1-Pad7)") (class "Default")
      (node (ref "P1") (pin "7") (pinfunction "7_7") (pintype "passive"))
    )
    (net (code "125") (name "unconnected-(P1-Pad8)") (class "Default")
      (node (ref "P1") (pin "8") (pinfunction "8_8") (pintype "passive"))
    )
    (net (code "126") (name "unconnected-(P2-Pad4)") (class "Default")
      (node (ref "P2") (pin "4") (pinfunction "4_4") (pintype "passive+no_connect"))
    )
    (net (code "127") (name "unconnected-(P2-Pad5)") (class "Default")
      (node (ref "P2") (pin "5") (pinfunction "5_5") (pintype "passive+no_connect"))
    )
    (net (code "128") (name "unconnected-(P2-Pad12)") (class "Default")
      (node (ref "P2") (pin "12") (pinfunction "12_12") (pintype "passive+no_connect"))
    )
    (net (code "129") (name "unconnected-(P2-Pad16)") (class "Default")
      (node (ref "P2") (pin "16") (pinfunction "16_16") (pintype "passive+no_connect"))
    )
    (net (code "130") (name "unconnected-(U1-SET-Pad7)") (class "Default")
      (node (ref "U1") (pin "7") (pinfunction "SET_7") (pintype "passive+no_connect"))
    )
    (net (code "131") (name "unconnected-(U2-SET-Pad7)") (class "Default")
      (node (ref "U2") (pin "7") (pinfunction "SET_7") (pintype "passive+no_connect"))
    )
    (net (code "132") (name "unconnected-(U3-SET-Pad7)") (class "Default")
      (node (ref "U3") (pin "7") (pinfunction "SET_7") (pintype "passive+no_connect"))
    )
    (net (code "133") (name "unconnected-(U4-SET-Pad7)") (class "Default")
      (node (ref "U4") (pin "7") (pinfunction "SET_7") (pintype "passive+no_connect"))
    )
    (net (code "134") (name "unconnected-(U5-DO-Pad5)") (class "Default")
      (node (ref "U5") (pin "5") (pinfunction "DO_5") (pintype "passive+no_connect"))
    )
    (net (code "135") (name "unconnected-(U5-OUTB-Pad3)") (class "Default")
      (node (ref "U5") (pin "3") (pinfunction "OUTB_3") (pintype "passive"))
    )
    (net (code "136") (name "unconnected-(U5-SET-Pad7)") (class "Default")
      (node (ref "U5") (pin "7") (pinfunction "SET_7") (pintype "passive+no_connect"))
    )
  )
)
